# lm2574.net
KiCad netlist of a schematic drawn in EAGLE
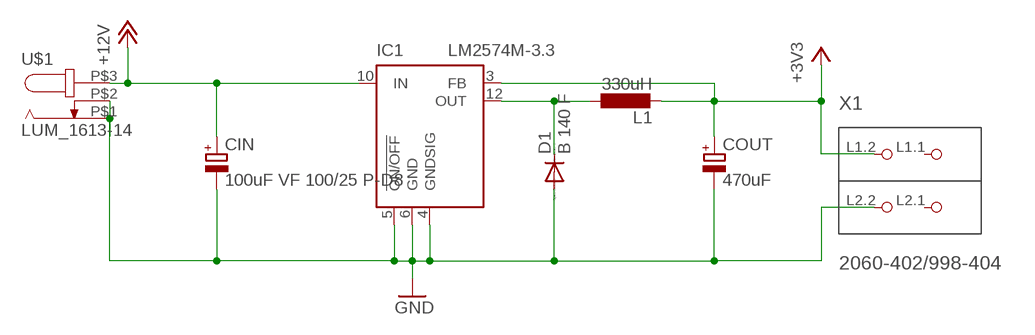
[diagram p0: schematic, sheet 1]

(export (version "E")
  (design (tool "Eeschema 10.0.6"))
  (components
    (comp (ref "CIN")
      (value "100uF VF 100/25 P-D8")
      (footprint "eagle-import:153CLV-0605")
      (libsource (lib "eagle-import") (part "resistor_CPOL-EU153CLV-0605"))
    )
    (comp (ref "COUT")
      (value "470uF")
      (footprint "eagle-import:153CLV-0810")
      (libsource (lib "eagle-import") (part "CPOL-EU153CLV-0810"))
    )
    (comp (ref "D1")
      (value "B 140 F")
      (footprint "eagle-import:DO-214AC")
      (libsource (lib "eagle-import") (part "DIODE-DO-214AC"))
    )
    (comp (ref "IC1")
      (value "LM2574M-3.3")
      (footprint "eagle-import:SO14W")
      (libsource (lib "eagle-import") (part "LM2574?-M3.3"))
    )
    (comp (ref "L1")
      (value "330uH")
      (footprint "eagle-import:PIS2816")
      (libsource (lib "eagle-import") (part "PIS4728"))
    )
    (comp (ref "U$1")
      (value "LUM_1613-14")
      (footprint "eagle-import:DCJ0202")
      (libsource (lib "eagle-import") (part "LUM_1613-14"))
    )
    (comp (ref "X1")
      (value "2060-402/998-404")
      (footprint "eagle-import:P-2060-402_998-404")
      (libsource (lib "eagle-import") (part "2060-402/998-404"))
    )
  )
  (nets
    (net (code "1") (name "+3V3") (class "Default")
      (node (ref "COUT") (pin "+") (pinfunction "+_+") (pintype "passive"))
      (node (ref "IC1") (pin "3") (pinfunction "FB_3") (pintype "input"))
      (node (ref "L1") (pin "2") (pinfunction "2_2") (pintype "passive"))
      (node (ref "X1") (pin "L1.2") (pinfunction "P1.2_L1.2") (pintype "bidirectional"))
    )
    (net (code "2") (name "+12V") (class "Default")
      (node (ref "CIN") (pin "+") (pinfunction "+_+") (pintype "passive"))
      (node (ref "IC1") (pin "10") (pinfunction "IN_10") (pintype "input"))
      (node (ref "U$1") (pin "P$3") (pinfunction "3_P$3") (pintype "passive"))
    )
    (net (code "3") (name "GND") (class "Default")
      (node (ref "CIN") (pin "-") (pinfunction "-_-") (pintype "passive"))
      (node (ref "COUT") (pin "-") (pinfunction "-_-") (pintype "passive"))
      (node (ref "D1") (pin "A") (pinfunction "A_A") (pintype "passive"))
      (node (ref "IC1") (pin "4") (pinfunction "GNDSIG_4") (pintype "input"))
      (node (ref "IC1") (pin "5") (pinfunction "~{ON/OFF}_5") (pintype "input"))
      (node (ref "IC1") (pin "6") (pinfunction "GND_6") (pintype "power_in"))
      (node (ref "U$1") (pin "P$1") (pinfunction "1_P$1") (pintype "passive"))
      (node (ref "U$1") (pin "P$2") (pinfunction "2_P$2") (pintype "passive"))
      (node (ref "X1") (pin "L2.2") (pinfunction "P2.2_L2.2") (pintype "bidirectional"))
    )
    (net (code "4") (name "Net-(IC1-OUT)") (class "Default")
      (node (ref "D1") (pin "C") (pinfunction "C_C") (pintype "passive"))
      (node (ref "IC1") (pin "12") (pinfunction "OUT_12") (pintype "passive"))
      (node (ref "L1") (pin "1") (pinfunction "1_1") (pintype "passive"))
    )
    (net (code "5") (name "unconnected-(X1-P1.1-PadL1.1)") (class "Default")
      (node (ref "X1") (pin "L1.1") (pinfunction "P1.1_L1.1") (pintype "bidirectional"))
    )
    (net (code "6") (name "unconnected-(X1-P2.1-PadL2.1)") (class "Default")
      (node (ref "X1") (pin "L2.1") (pinfunction "P2.1_L2.1") (pintype "bidirectional"))
    )
  )
)
